# clock_v0_3.net
KiCad netlist of a schematic drawn in EAGLE
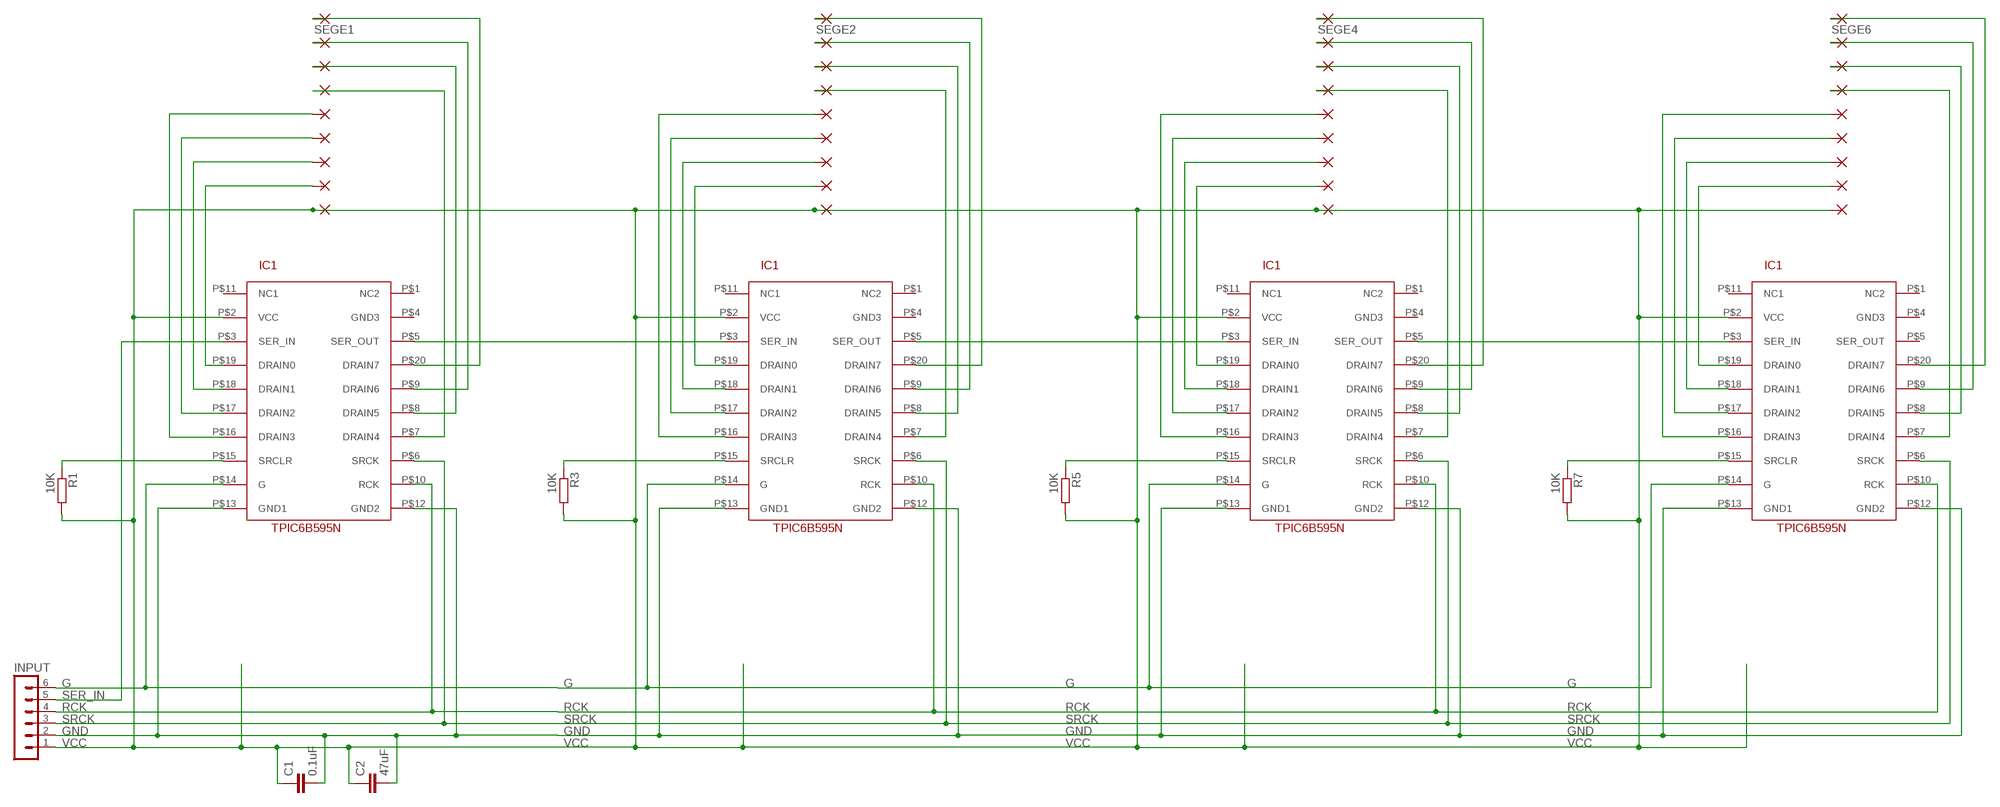
[diagram p0: schematic, sheet 1]

(export (version "E")
  (design (tool "Eeschema 10.0.6"))
  (components
    (comp (ref "C1")
      (value "0.1uF")
      (footprint "eagle-import:RCL_C025-025X050")
      (libsource (lib "eagle-import") (part "RCL_C-EU025-025X050"))
    )
    (comp (ref "C2")
      (value "47uF")
      (footprint "eagle-import:RCL_C025-025X050")
      (libsource (lib "eagle-import") (part "RCL_C-EU025-025X050"))
    )
    (comp (ref "DEC1")
      (value "1,6/0,8")
      (footprint "eagle-import:1,6_0,8")
      (libsource (lib "eagle-import") (part "1,6/0,8"))
    )
    (comp (ref "DEC2")
      (value "1,6/0,8")
      (footprint "eagle-import:1,6_0,8")
      (libsource (lib "eagle-import") (part "1,6/0,8"))
    )
    (comp (ref "DEC4")
      (value "1,6/0,8")
      (footprint "eagle-import:1,6_0,8")
      (libsource (lib "eagle-import") (part "1,6/0,8"))
    )
    (comp (ref "DEC6")
      (value "1,6/0,8")
      (footprint "eagle-import:1,6_0,8")
      (libsource (lib "eagle-import") (part "1,6/0,8"))
    )
    (comp (ref "INPUT")
      (value "CON-LSTB_MA06-1")
      (footprint "eagle-import:CON-LSTB_MA06-1")
      (libsource (lib "eagle-import") (part "CON-LSTB_MA06-1"))
    )
    (comp (ref "R1")
      (value "10K")
      (footprint "eagle-import:RCL_0207_7")
      (libsource (lib "eagle-import") (part "RCL_R-EU_0207/7"))
    )
    (comp (ref "R3")
      (value "10K")
      (footprint "eagle-import:RCL_0207_7")
      (libsource (lib "eagle-import") (part "RCL_R-EU_0207/7"))
    )
    (comp (ref "R5")
      (value "10K")
      (footprint "eagle-import:RCL_0207_7")
      (libsource (lib "eagle-import") (part "RCL_R-EU_0207/7"))
    )
    (comp (ref "R7")
      (value "10K")
      (footprint "eagle-import:RCL_0207_7")
      (libsource (lib "eagle-import") (part "RCL_R-EU_0207/7"))
    )
    (comp (ref "SEGA1")
      (value "1,6/0,8")
      (footprint "eagle-import:1,6_0,8")
      (libsource (lib "eagle-import") (part "1,6/0,8"))
    )
    (comp (ref "SEGA2")
      (value "1,6/0,8")
      (footprint "eagle-import:1,6_0,8")
      (libsource (lib "eagle-import") (part "1,6/0,8"))
    )
    (comp (ref "SEGA4")
      (value "1,6/0,8")
      (footprint "eagle-import:1,6_0,8")
      (libsource (lib "eagle-import") (part "1,6/0,8"))
    )
    (comp (ref "SEGA6")
      (value "1,6/0,8")
      (footprint "eagle-import:1,6_0,8")
      (libsource (lib "eagle-import") (part "1,6/0,8"))
    )
    (comp (ref "SEGB1")
      (value "1,6/0,8")
      (footprint "eagle-import:1,6_0,8")
      (libsource (lib "eagle-import") (part "1,6/0,8"))
    )
    (comp (ref "SEGB2")
      (value "1,6/0,8")
      (footprint "eagle-import:1,6_0,8")
      (libsource (lib "eagle-import") (part "1,6/0,8"))
    )
    (comp (ref "SEGB4")
      (value "1,6/0,8")
      (footprint "eagle-import:1,6_0,8")
      (libsource (lib "eagle-import") (part "1,6/0,8"))
    )
    (comp (ref "SEGB6")
      (value "1,6/0,8")
      (footprint "eagle-import:1,6_0,8")
      (libsource (lib "eagle-import") (part "1,6/0,8"))
    )
    (comp (ref "SEGC1")
      (value "1,6/0,8")
      (footprint "eagle-import:1,6_0,8")
      (libsource (lib "eagle-import") (part "1,6/0,8"))
    )
    (comp (ref "SEGC2")
      (value "1,6/0,8")
      (footprint "eagle-import:1,6_0,8")
      (libsource (lib "eagle-import") (part "1,6/0,8"))
    )
    (comp (ref "SEGC4")
      (value "1,6/0,8")
      (footprint "eagle-import:1,6_0,8")
      (libsource (lib "eagle-import") (part "1,6/0,8"))
    )
    (comp (ref "SEGC6")
      (value "1,6/0,8")
      (footprint "eagle-import:1,6_0,8")
      (libsource (lib "eagle-import") (part "1,6/0,8"))
    )
    (comp (ref "SEGD1")
      (value "1,6/0,8")
      (footprint "eagle-import:1,6_0,8")
      (libsource (lib "eagle-import") (part "1,6/0,8"))
    )
    (comp (ref "SEGD2")
      (value "1,6/0,8")
      (footprint "eagle-import:1,6_0,8")
      (libsource (lib "eagle-import") (part "1,6/0,8"))
    )
    (comp (ref "SEGD4")
      (value "1,6/0,8")
      (footprint "eagle-import:1,6_0,8")
      (libsource (lib "eagle-import") (part "1,6/0,8"))
    )
    (comp (ref "SEGD6")
      (value "1,6/0,8")
      (footprint "eagle-import:1,6_0,8")
      (libsource (lib "eagle-import") (part "1,6/0,8"))
    )
    (comp (ref "SEGE1")
      (value "1,6/0,8")
      (footprint "eagle-import:1,6_0,8")
      (libsource (lib "eagle-import") (part "1,6/0,8"))
    )
    (comp (ref "SEGE2")
      (value "1,6/0,8")
      (footprint "eagle-import:1,6_0,8")
      (libsource (lib "eagle-import") (part "1,6/0,8"))
    )
    (comp (ref "SEGE4")
      (value "1,6/0,8")
      (footprint "eagle-import:1,6_0,8")
      (libsource (lib "eagle-import") (part "1,6/0,8"))
    )
    (comp (ref "SEGE6")
      (value "1,6/0,8")
      (footprint "eagle-import:1,6_0,8")
      (libsource (lib "eagle-import") (part "1,6/0,8"))
    )
    (comp (ref "SEGF1")
      (value "1,6/0,8")
      (footprint "eagle-import:1,6_0,8")
      (libsource (lib "eagle-import") (part "1,6/0,8"))
    )
    (comp (ref "SEGF2")
      (value "1,6/0,8")
      (footprint "eagle-import:1,6_0,8")
      (libsource (lib "eagle-import") (part "1,6/0,8"))
    )
    (comp (ref "SEGF4")
      (value "1,6/0,8")
      (footprint "eagle-import:1,6_0,8")
      (libsource (lib "eagle-import") (part "1,6/0,8"))
    )
    (comp (ref "SEGF6")
      (value "1,6/0,8")
      (footprint "eagle-import:1,6_0,8")
      (libsource (lib "eagle-import") (part "1,6/0,8"))
    )
    (comp (ref "SEGG1")
      (value "1,6/0,8")
      (footprint "eagle-import:1,6_0,8")
      (libsource (lib "eagle-import") (part "1,6/0,8"))
    )
    (comp (ref "SEGG2")
      (value "1,6/0,8")
      (footprint "eagle-import:1,6_0,8")
      (libsource (lib "eagle-import") (part "1,6/0,8"))
    )
    (comp (ref "SEGG4")
      (value "1,6/0,8")
      (footprint "eagle-import:1,6_0,8")
      (libsource (lib "eagle-import") (part "1,6/0,8"))
    )
    (comp (ref "SEGG6")
      (value "1,6/0,8")
      (footprint "eagle-import:1,6_0,8")
      (libsource (lib "eagle-import") (part "1,6/0,8"))
    )
    (comp (ref "U$1")
      (value "TPIC6B595N_TPIC6B595NPDIP-20")
      (footprint "eagle-import:TPIC6B595N_PDIP-20")
      (libsource (lib "eagle-import") (part "TPIC6B595N_TPIC6B595NPDIP-20"))
    )
    (comp (ref "U$3")
      (value "TPIC6B595N_TPIC6B595NPDIP-20")
      (footprint "eagle-import:TPIC6B595N_PDIP-20")
      (libsource (lib "eagle-import") (part "TPIC6B595N_TPIC6B595NPDIP-20"))
    )
    (comp (ref "U$5")
      (value "TPIC6B595N_TPIC6B595NPDIP-20")
      (footprint "eagle-import:TPIC6B595N_PDIP-20")
      (libsource (lib "eagle-import") (part "TPIC6B595N_TPIC6B595NPDIP-20"))
    )
    (comp (ref "U$7")
      (value "TPIC6B595N_TPIC6B595NPDIP-20")
      (footprint "eagle-import:TPIC6B595N_PDIP-20")
      (libsource (lib "eagle-import") (part "TPIC6B595N_TPIC6B595NPDIP-20"))
    )
    (comp (ref "VCC1")
      (value "1,6/0,8")
      (footprint "eagle-import:1,6_0,8")
      (libsource (lib "eagle-import") (part "1,6/0,8"))
    )
    (comp (ref "VCC2")
      (value "1,6/0,8")
      (footprint "eagle-import:1,6_0,8")
      (libsource (lib "eagle-import") (part "1,6/0,8"))
    )
    (comp (ref "VCC4")
      (value "1,6/0,8")
      (footprint "eagle-import:1,6_0,8")
      (libsource (lib "eagle-import") (part "1,6/0,8"))
    )
    (comp (ref "VCC6")
      (value "1,6/0,8")
      (footprint "eagle-import:1,6_0,8")
      (libsource (lib "eagle-import") (part "1,6/0,8"))
    )
  )
  (nets
    (net (code "1") (name "/G") (class "Default")
      (node (ref "INPUT") (pin "6") (pinfunction "6_6") (pintype "passive"))
      (node (ref "U$1") (pin "P$14") (pinfunction "G_P$14") (pintype "bidirectional"))
      (node (ref "U$3") (pin "P$14") (pinfunction "G_P$14") (pintype "bidirectional"))
      (node (ref "U$5") (pin "P$14") (pinfunction "G_P$14") (pintype "bidirectional"))
      (node (ref "U$7") (pin "P$14") (pinfunction "G_P$14") (pintype "bidirectional"))
    )
    (net (code "2") (name "/GND") (class "Default")
      (node (ref "C1") (pin "2") (pinfunction "2_2") (pintype "passive"))
      (node (ref "C2") (pin "2") (pinfunction "2_2") (pintype "passive"))
      (node (ref "INPUT") (pin "2") (pinfunction "2_2") (pintype "passive"))
      (node (ref "U$1") (pin "P$12") (pinfunction "GND2_P$12") (pintype "bidirectional"))
      (node (ref "U$1") (pin "P$13") (pinfunction "GND1_P$13") (pintype "bidirectional"))
      (node (ref "U$3") (pin "P$12") (pinfunction "GND2_P$12") (pintype "bidirectional"))
      (node (ref "U$3") (pin "P$13") (pinfunction "GND1_P$13") (pintype "bidirectional"))
      (node (ref "U$5") (pin "P$12") (pinfunction "GND2_P$12") (pintype "bidirectional"))
      (node (ref "U$5") (pin "P$13") (pinfunction "GND1_P$13") (pintype "bidirectional"))
      (node (ref "U$7") (pin "P$12") (pinfunction "GND2_P$12") (pintype "bidirectional"))
      (node (ref "U$7") (pin "P$13") (pinfunction "GND1_P$13") (pintype "bidirectional"))
    )
    (net (code "3") (name "/RCK") (class "Default")
      (node (ref "INPUT") (pin "4") (pinfunction "4_4") (pintype "passive"))
      (node (ref "U$1") (pin "P$10") (pinfunction "RCK_P$10") (pintype "bidirectional"))
      (node (ref "U$3") (pin "P$10") (pinfunction "RCK_P$10") (pintype "bidirectional"))
      (node (ref "U$5") (pin "P$10") (pinfunction "RCK_P$10") (pintype "bidirectional"))
      (node (ref "U$7") (pin "P$10") (pinfunction "RCK_P$10") (pintype "bidirectional"))
    )
    (net (code "4") (name "/SER_IN") (class "Default")
      (node (ref "INPUT") (pin "5") (pinfunction "5_5") (pintype "passive"))
      (node (ref "U$1") (pin "P$3") (pinfunction "SER_IN_P$3") (pintype "bidirectional"))
    )
    (net (code "5") (name "/SRCK") (class "Default")
      (node (ref "INPUT") (pin "3") (pinfunction "3_3") (pintype "passive"))
      (node (ref "U$1") (pin "P$6") (pinfunction "SRCK_P$6") (pintype "bidirectional"))
      (node (ref "U$3") (pin "P$6") (pinfunction "SRCK_P$6") (pintype "bidirectional"))
      (node (ref "U$5") (pin "P$6") (pinfunction "SRCK_P$6") (pintype "bidirectional"))
      (node (ref "U$7") (pin "P$6") (pinfunction "SRCK_P$6") (pintype "bidirectional"))
    )
    (net (code "6") (name "/VCC") (class "Default")
      (node (ref "C1") (pin "1") (pinfunction "1_1") (pintype "passive"))
      (node (ref "C2") (pin "1") (pinfunction "1_1") (pintype "passive"))
      (node (ref "INPUT") (pin "1") (pinfunction "1_1") (pintype "passive"))
      (node (ref "R1") (pin "2") (pinfunction "2_2") (pintype "passive"))
      (node (ref "R3") (pin "2") (pinfunction "2_2") (pintype "passive"))
      (node (ref "R5") (pin "2") (pinfunction "2_2") (pintype "passive"))
      (node (ref "R7") (pin "2") (pinfunction "2_2") (pintype "passive"))
      (node (ref "SEGD1") (pin "1") (pinfunction "P_1") (pintype "passive"))
      (node (ref "SEGD2") (pin "1") (pinfunction "P_1") (pintype "passive"))
      (node (ref "SEGD4") (pin "1") (pinfunction "P_1") (pintype "passive"))
      (node (ref "SEGD6") (pin "1") (pinfunction "P_1") (pintype "passive"))
      (node (ref "U$1") (pin "P$2") (pinfunction "VCC_P$2") (pintype "bidirectional"))
      (node (ref "U$3") (pin "P$2") (pinfunction "VCC_P$2") (pintype "bidirectional"))
      (node (ref "U$5") (pin "P$2") (pinfunction "VCC_P$2") (pintype "bidirectional"))
      (node (ref "U$7") (pin "P$2") (pinfunction "VCC_P$2") (pintype "bidirectional"))
    )
    (net (code "7") (name "Net-(DEC1-P)") (class "Default")
      (node (ref "DEC1") (pin "1") (pinfunction "P_1") (pintype "passive"))
      (node (ref "U$1") (pin "P$18") (pinfunction "DRAIN1_P$18") (pintype "bidirectional"))
    )
    (net (code "8") (name "Net-(DEC2-P)") (class "Default")
      (node (ref "DEC2") (pin "1") (pinfunction "P_1") (pintype "passive"))
      (node (ref "U$3") (pin "P$18") (pinfunction "DRAIN1_P$18") (pintype "bidirectional"))
    )
    (net (code "9") (name "Net-(DEC4-P)") (class "Default")
      (node (ref "DEC4") (pin "1") (pinfunction "P_1") (pintype "passive"))
      (node (ref "U$5") (pin "P$18") (pinfunction "DRAIN1_P$18") (pintype "bidirectional"))
    )
    (net (code "10") (name "Net-(DEC6-P)") (class "Default")
      (node (ref "DEC6") (pin "1") (pinfunction "P_1") (pintype "passive"))
      (node (ref "U$7") (pin "P$18") (pinfunction "DRAIN1_P$18") (pintype "bidirectional"))
    )
    (net (code "11") (name "Net-(SEGA1-P)") (class "Default")
      (node (ref "SEGA1") (pin "1") (pinfunction "P_1") (pintype "passive"))
      (node (ref "U$1") (pin "P$7") (pinfunction "DRAIN4_P$7") (pintype "bidirectional"))
    )
    (net (code "12") (name "Net-(SEGA2-P)") (class "Default")
      (node (ref "SEGA2") (pin "1") (pinfunction "P_1") (pintype "passive"))
      (node (ref "U$3") (pin "P$7") (pinfunction "DRAIN4_P$7") (pintype "bidirectional"))
    )
    (net (code "13") (name "Net-(SEGA4-P)") (class "Default")
      (node (ref "SEGA4") (pin "1") (pinfunction "P_1") (pintype "passive"))
      (node (ref "U$5") (pin "P$7") (pinfunction "DRAIN4_P$7") (pintype "bidirectional"))
    )
    (net (code "14") (name "Net-(SEGA6-P)") (class "Default")
      (node (ref "SEGA6") (pin "1") (pinfunction "P_1") (pintype "passive"))
      (node (ref "U$7") (pin "P$7") (pinfunction "DRAIN4_P$7") (pintype "bidirectional"))
    )
    (net (code "15") (name "Net-(SEGB1-P)") (class "Default")
      (node (ref "SEGB1") (pin "1") (pinfunction "P_1") (pintype "passive"))
      (node (ref "U$1") (pin "P$17") (pinfunction "DRAIN2_P$17") (pintype "bidirectional"))
    )
    (net (code "16") (name "Net-(SEGB2-P)") (class "Default")
      (node (ref "SEGB2") (pin "1") (pinfunction "P_1") (pintype "passive"))
      (node (ref "U$3") (pin "P$17") (pinfunction "DRAIN2_P$17") (pintype "bidirectional"))
    )
    (net (code "17") (name "Net-(SEGB4-P)") (class "Default")
      (node (ref "SEGB4") (pin "1") (pinfunction "P_1") (pintype "passive"))
      (node (ref "U$5") (pin "P$17") (pinfunction "DRAIN2_P$17") (pintype "bidirectional"))
    )
    (net (code "18") (name "Net-(SEGB6-P)") (class "Default")
      (node (ref "SEGB6") (pin "1") (pinfunction "P_1") (pintype "passive"))
      (node (ref "U$7") (pin "P$17") (pinfunction "DRAIN2_P$17") (pintype "bidirectional"))
    )
    (net (code "19") (name "Net-(SEGC1-P)") (class "Default")
      (node (ref "SEGC1") (pin "1") (pinfunction "P_1") (pintype "passive"))
      (node (ref "U$1") (pin "P$16") (pinfunction "DRAIN3_P$16") (pintype "bidirectional"))
    )
    (net (code "20") (name "Net-(SEGC2-P)") (class "Default")
      (node (ref "SEGC2") (pin "1") (pinfunction "P_1") (pintype "passive"))
      (node (ref "U$3") (pin "P$16") (pinfunction "DRAIN3_P$16") (pintype "bidirectional"))
    )
    (net (code "21") (name "Net-(SEGC4-P)") (class "Default")
      (node (ref "SEGC4") (pin "1") (pinfunction "P_1") (pintype "passive"))
      (node (ref "U$5") (pin "P$16") (pinfunction "DRAIN3_P$16") (pintype "bidirectional"))
    )
    (net (code "22") (name "Net-(SEGC6-P)") (class "Default")
      (node (ref "SEGC6") (pin "1") (pinfunction "P_1") (pintype "passive"))
      (node (ref "U$7") (pin "P$16") (pinfunction "DRAIN3_P$16") (pintype "bidirectional"))
    )
    (net (code "23") (name "Net-(SEGE1-P)") (class "Default")
      (node (ref "SEGE1") (pin "1") (pinfunction "P_1") (pintype "passive"))
      (node (ref "U$1") (pin "P$20") (pinfunction "DRAIN7_P$20") (pintype "bidirectional"))
    )
    (net (code "24") (name "Net-(SEGE2-P)") (class "Default")
      (node (ref "SEGE2") (pin "1") (pinfunction "P_1") (pintype "passive"))
      (node (ref "U$3") (pin "P$20") (pinfunction "DRAIN7_P$20") (pintype "bidirectional"))
    )
    (net (code "25") (name "Net-(SEGE4-P)") (class "Default")
      (node (ref "SEGE4") (pin "1") (pinfunction "P_1") (pintype "passive"))
      (node (ref "U$5") (pin "P$20") (pinfunction "DRAIN7_P$20") (pintype "bidirectional"))
    )
    (net (code "26") (name "Net-(SEGE6-P)") (class "Default")
      (node (ref "SEGE6") (pin "1") (pinfunction "P_1") (pintype "passive"))
      (node (ref "U$7") (pin "P$20") (pinfunction "DRAIN7_P$20") (pintype "bidirectional"))
    )
    (net (code "27") (name "Net-(SEGF1-P)") (class "Default")
      (node (ref "SEGF1") (pin "1") (pinfunction "P_1") (pintype "passive"))
      (node (ref "U$1") (pin "P$8") (pinfunction "DRAIN5_P$8") (pintype "bidirectional"))
    )
    (net (code "28") (name "Net-(SEGF2-P)") (class "Default")
      (node (ref "SEGF2") (pin "1") (pinfunction "P_1") (pintype "passive"))
      (node (ref "U$3") (pin "P$8") (pinfunction "DRAIN5_P$8") (pintype "bidirectional"))
    )
    (net (code "29") (name "Net-(SEGF4-P)") (class "Default")
      (node (ref "SEGF4") (pin "1") (pinfunction "P_1") (pintype "passive"))
      (node (ref "U$5") (pin "P$8") (pinfunction "DRAIN5_P$8") (pintype "bidirectional"))
    )
    (net (code "30") (name "Net-(SEGF6-P)") (class "Default")
      (node (ref "SEGF6") (pin "1") (pinfunction "P_1") (pintype "passive"))
      (node (ref "U$7") (pin "P$8") (pinfunction "DRAIN5_P$8") (pintype "bidirectional"))
    )
    (net (code "31") (name "Net-(SEGG1-P)") (class "Default")
      (node (ref "SEGG1") (pin "1") (pinfunction "P_1") (pintype "passive"))
      (node (ref "U$1") (pin "P$9") (pinfunction "DRAIN6_P$9") (pintype "bidirectional"))
    )
    (net (code "32") (name "Net-(SEGG2-P)") (class "Default")
      (node (ref "SEGG2") (pin "1") (pinfunction "P_1") (pintype "passive"))
      (node (ref "U$3") (pin "P$9") (pinfunction "DRAIN6_P$9") (pintype "bidirectional"))
    )
    (net (code "33") (name "Net-(SEGG4-P)") (class "Default")
      (node (ref "SEGG4") (pin "1") (pinfunction "P_1") (pintype "passive"))
      (node (ref "U$5") (pin "P$9") (pinfunction "DRAIN6_P$9") (pintype "bidirectional"))
    )
    (net (code "34") (name "Net-(SEGG6-P)") (class "Default")
      (node (ref "SEGG6") (pin "1") (pinfunction "P_1") (pintype "passive"))
      (node (ref "U$7") (pin "P$9") (pinfunction "DRAIN6_P$9") (pintype "bidirectional"))
    )
    (net (code "35") (name "Net-(U$1-DRAIN0)") (class "Default")
      (node (ref "U$1") (pin "P$19") (pinfunction "DRAIN0_P$19") (pintype "bidirectional"))
      (node (ref "VCC1") (pin "1") (pinfunction "P_1") (pintype "passive"))
    )
    (net (code "36") (name "Net-(U$1-SER_OUT)") (class "Default")
      (node (ref "U$1") (pin "P$5") (pinfunction "SER_OUT_P$5") (pintype "bidirectional"))
      (node (ref "U$3") (pin "P$3") (pinfunction "SER_IN_P$3") (pintype "bidirectional"))
    )
    (net (code "37") (name "Net-(U$1-SRCLR)") (class "Default")
      (node (ref "R1") (pin "1") (pinfunction "1_1") (pintype "passive"))
      (node (ref "U$1") (pin "P$15") (pinfunction "SRCLR_P$15") (pintype "bidirectional"))
    )
    (net (code "38") (name "Net-(U$3-DRAIN0)") (class "Default")
      (node (ref "U$3") (pin "P$19") (pinfunction "DRAIN0_P$19") (pintype "bidirectional"))
      (node (ref "VCC2") (pin "1") (pinfunction "P_1") (pintype "passive"))
    )
    (net (code "39") (name "Net-(U$3-SER_OUT)") (class "Default")
      (node (ref "U$3") (pin "P$5") (pinfunction "SER_OUT_P$5") (pintype "bidirectional"))
      (node (ref "U$5") (pin "P$3") (pinfunction "SER_IN_P$3") (pintype "bidirectional"))
    )
    (net (code "40") (name "Net-(U$3-SRCLR)") (class "Default")
      (node (ref "R3") (pin "1") (pinfunction "1_1") (pintype "passive"))
      (node (ref "U$3") (pin "P$15") (pinfunction "SRCLR_P$15") (pintype "bidirectional"))
    )
    (net (code "41") (name "Net-(U$5-DRAIN0)") (class "Default")
      (node (ref "U$5") (pin "P$19") (pinfunction "DRAIN0_P$19") (pintype "bidirectional"))
      (node (ref "VCC4") (pin "1") (pinfunction "P_1") (pintype "passive"))
    )
    (net (code "42") (name "Net-(U$5-SER_OUT)") (class "Default")
      (node (ref "U$5") (pin "P$5") (pinfunction "SER_OUT_P$5") (pintype "bidirectional"))
      (node (ref "U$7") (pin "P$3") (pinfunction "SER_IN_P$3") (pintype "bidirectional"))
    )
    (net (code "43") (name "Net-(U$5-SRCLR)") (class "Default")
      (node (ref "R5") (pin "1") (pinfunction "1_1") (pintype "passive"))
      (node (ref "U$5") (pin "P$15") (pinfunction "SRCLR_P$15") (pintype "bidirectional"))
    )
    (net (code "44") (name "Net-(U$7-DRAIN0)") (class "Default")
      (node (ref "U$7") (pin "P$19") (pinfunction "DRAIN0_P$19") (pintype "bidirectional"))
      (node (ref "VCC6") (pin "1") (pinfunction "P_1") (pintype "passive"))
    )
    (net (code "45") (name "Net-(U$7-SRCLR)") (class "Default")
      (node (ref "R7") (pin "1") (pinfunction "1_1") (pintype "passive"))
      (node (ref "U$7") (pin "P$15") (pinfunction "SRCLR_P$15") (pintype "bidirectional"))
    )
    (net (code "46") (name "unconnected-(U$1-GND3-PadP$4)") (class "Default")
      (node (ref "U$1") (pin "P$4") (pinfunction "GND3_P$4") (pintype "bidirectional"))
    )
    (net (code "47") (name "unconnected-(U$1-NC1-PadP$11)") (class "Default")
      (node (ref "U$1") (pin "P$11") (pinfunction "NC1_P$11") (pintype "bidirectional"))
    )
    (net (code "48") (name "unconnected-(U$1-NC2-PadP$1)") (class "Default")
      (node (ref "U$1") (pin "P$1") (pinfunction "NC2_P$1") (pintype "bidirectional"))
    )
    (net (code "49") (name "unconnected-(U$3-GND3-PadP$4)") (class "Default")
      (node (ref "U$3") (pin "P$4") (pinfunction "GND3_P$4") (pintype "bidirectional"))
    )
    (net (code "50") (name "unconnected-(U$3-NC1-PadP$11)") (class "Default")
      (node (ref "U$3") (pin "P$11") (pinfunction "NC1_P$11") (pintype "bidirectional"))
    )
    (net (code "51") (name "unconnected-(U$3-NC2-PadP$1)") (class "Default")
      (node (ref "U$3") (pin "P$1") (pinfunction "NC2_P$1") (pintype "bidirectional"))
    )
    (net (code "52") (name "unconnected-(U$5-GND3-PadP$4)") (class "Default")
      (node (ref "U$5") (pin "P$4") (pinfunction "GND3_P$4") (pintype "bidirectional"))
    )
    (net (code "53") (name "unconnected-(U$5-NC1-PadP$11)") (class "Default")
      (node (ref "U$5") (pin "P$11") (pinfunction "NC1_P$11") (pintype "bidirectional"))
    )
    (net (code "54") (name "unconnected-(U$5-NC2-PadP$1)") (class "Default")
      (node (ref "U$5") (pin "P$1") (pinfunction "NC2_P$1") (pintype "bidirectional"))
    )
    (net (code "55") (name "unconnected-(U$7-GND3-PadP$4)") (class "Default")
      (node (ref "U$7") (pin "P$4") (pinfunction "GND3_P$4") (pintype "bidirectional"))
    )
    (net (code "56") (name "unconnected-(U$7-NC1-PadP$11)") (class "Default")
      (node (ref "U$7") (pin "P$11") (pinfunction "NC1_P$11") (pintype "bidirectional"))
    )
    (net (code "57") (name "unconnected-(U$7-NC2-PadP$1)") (class "Default")
      (node (ref "U$7") (pin "P$1") (pinfunction "NC2_P$1") (pintype "bidirectional"))
    )
    (net (code "58") (name "unconnected-(U$7-SER_OUT-PadP$5)") (class "Default")
      (node (ref "U$7") (pin "P$5") (pinfunction "SER_OUT_P$5") (pintype "bidirectional"))
    )
  )
)
